# Adafruit_DS2482S-800_Breakout.net
KiCad netlist of a schematic drawn in EAGLE
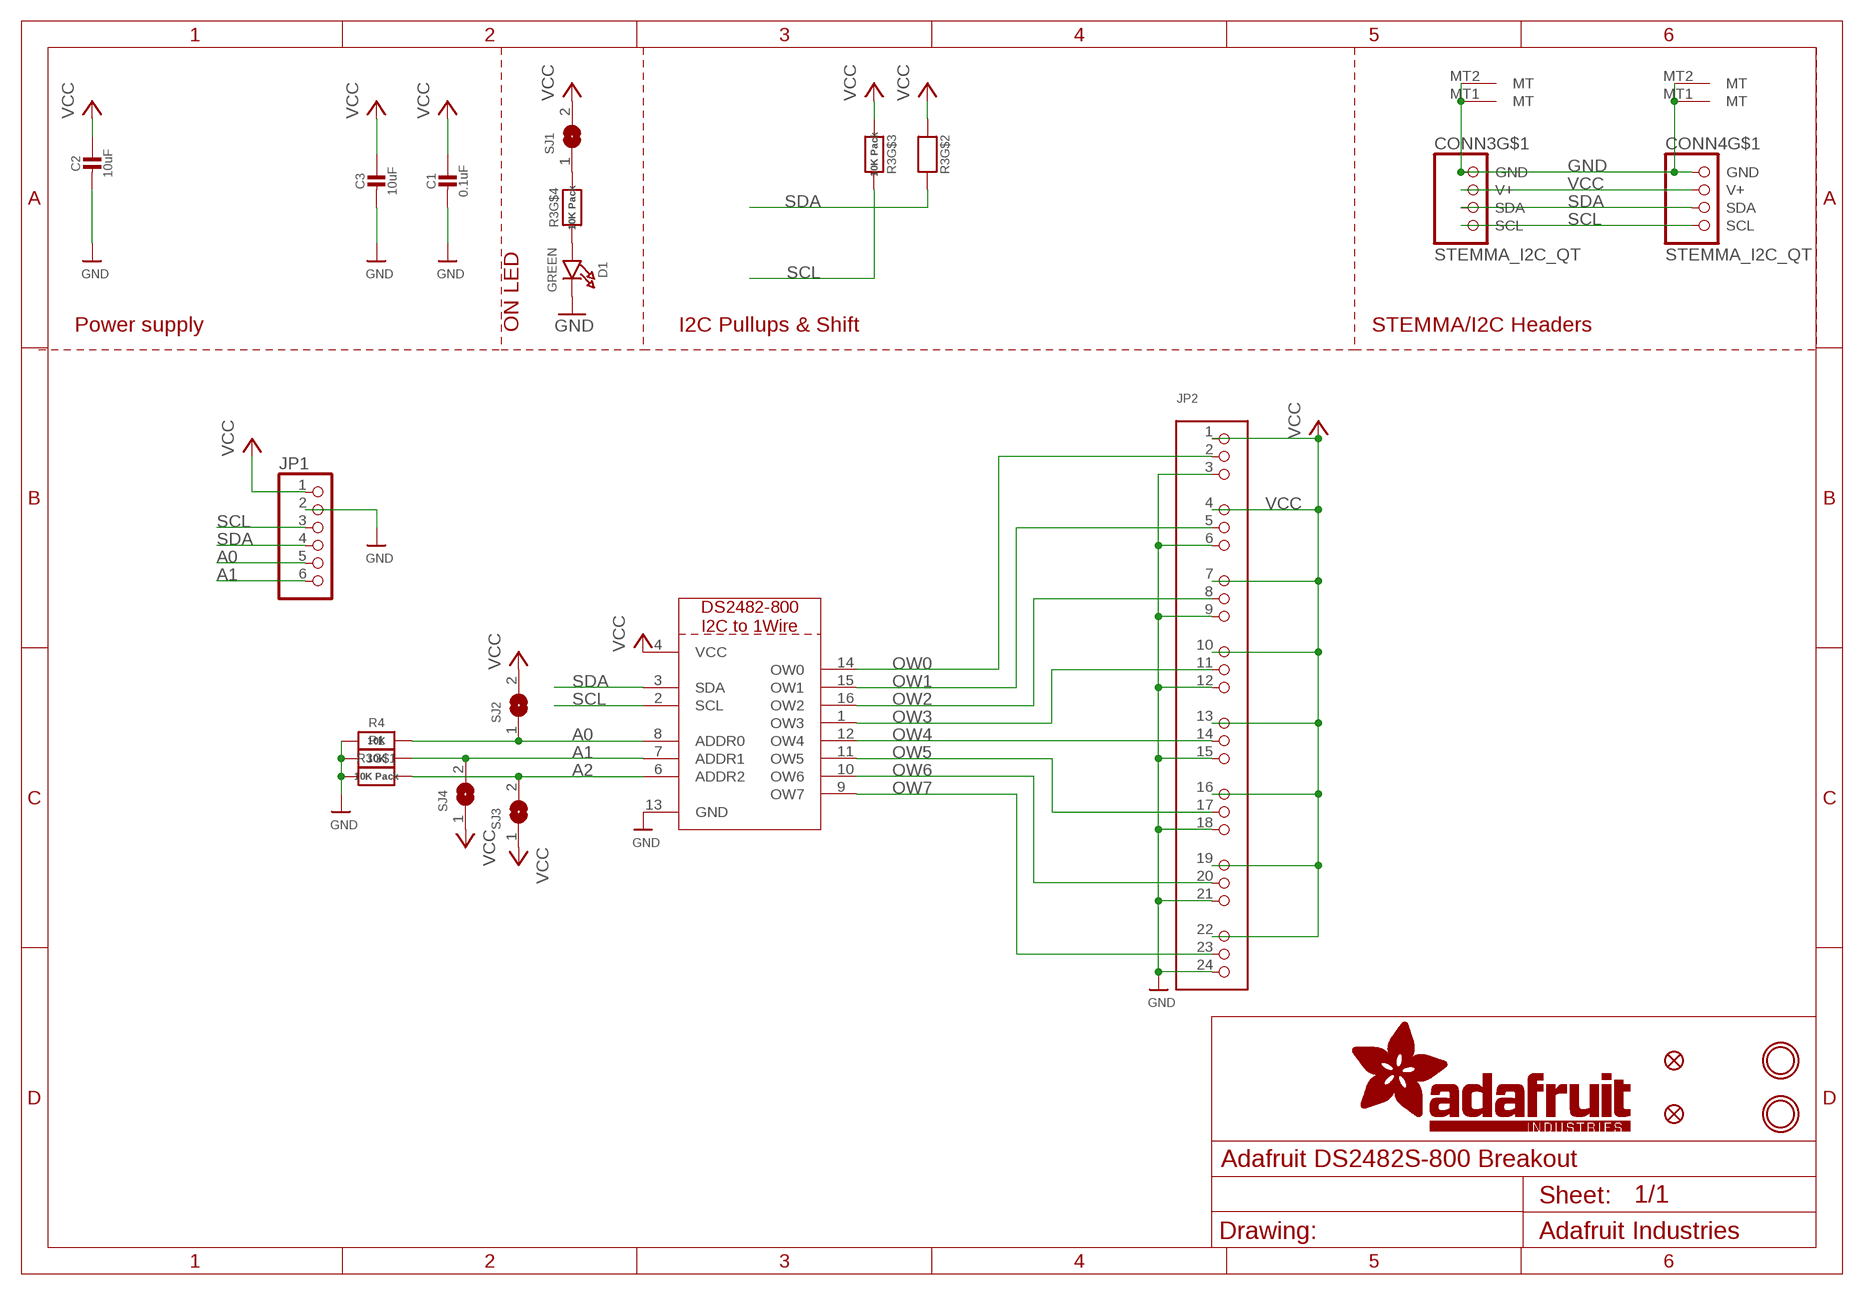
[diagram p0: schematic, sheet 1]

(export (version "E")
  (design (tool "Eeschema 10.0.6"))
  (components
    (comp (ref "C1")
      (value "0.1uF")
      (footprint "eagle-import:0603-NO")
      (libsource (lib "eagle-import") (part "CAP_CERAMIC0603_NO"))
    )
    (comp (ref "C2")
      (value "10uF")
      (footprint "eagle-import:0805-NO")
      (libsource (lib "eagle-import") (part "CAP_CERAMIC0805-NOOUTLINE"))
    )
    (comp (ref "C3")
      (value "10uF")
      (footprint "eagle-import:0805-NO")
      (libsource (lib "eagle-import") (part "CAP_CERAMIC0805-NOOUTLINE"))
    )
    (comp (ref "CONN3")
      (value "STEMMA_I2C_QT")
      (footprint "eagle-import:JST_SH4")
      (libsource (lib "eagle-import") (part "STEMMA_I2C_QT"))
    )
    (comp (ref "CONN4")
      (value "STEMMA_I2C_QT")
      (footprint "eagle-import:JST_SH4")
      (libsource (lib "eagle-import") (part "STEMMA_I2C_QT"))
    )
    (comp (ref "D1")
      (value "GREEN")
      (footprint "eagle-import:CHIPLED_0603_NOOUTLINE")
      (libsource (lib "eagle-import") (part "LED0603_NOOUTLINE"))
    )
    (comp (ref "FID3")
      (value "FIDUCIAL_1MM")
      (footprint "eagle-import:FIDUCIAL_1MM")
      (libsource (lib "eagle-import") (part "FIDUCIAL_1MM"))
    )
    (comp (ref "FID4")
      (value "FIDUCIAL_1MM")
      (footprint "eagle-import:FIDUCIAL_1MM")
      (libsource (lib "eagle-import") (part "FIDUCIAL_1MM"))
    )
    (comp (ref "JP1")
      (value "HEADER-1X670MIL")
      (footprint "eagle-import:1X06_ROUND_70")
      (libsource (lib "eagle-import") (part "HEADER-1X670MIL"))
    )
    (comp (ref "JP2")
      (value "HEADER-3X08")
      (footprint "eagle-import:3X08")
      (libsource (lib "eagle-import") (part "HEADER-3X08"))
    )
    (comp (ref "R1")
      (value "10K")
      (footprint "eagle-import:0603-NO")
      (libsource (lib "eagle-import") (part "RESISTOR_0603_NOOUT"))
    )
    (comp (ref "R3")
      (value "10K Pack")
      (footprint "eagle-import:RESPACK_4X0603")
      (libsource (lib "eagle-import") (part "RESISTOR_4PACK"))
    )
    (comp (ref "R4")
      (value "10K")
      (footprint "eagle-import:0603-NO")
      (libsource (lib "eagle-import") (part "RESISTOR_0603_NOOUT"))
    )
    (comp (ref "SJ1")
      (value "SOLDERJUMPERCLOSED")
      (footprint "eagle-import:SOLDERJUMPER_CLOSEDWIRE")
      (libsource (lib "eagle-import") (part "SOLDERJUMPERCLOSED"))
    )
    (comp (ref "SJ2")
      (value "SOLDERJUMPER")
      (footprint "eagle-import:SOLDERJUMPER_ARROW_NOPASTE")
      (libsource (lib "eagle-import") (part "SOLDERJUMPER"))
    )
    (comp (ref "SJ3")
      (value "SOLDERJUMPER")
      (footprint "eagle-import:SOLDERJUMPER_ARROW_NOPASTE")
      (libsource (lib "eagle-import") (part "SOLDERJUMPER"))
    )
    (comp (ref "SJ4")
      (value "SOLDERJUMPER")
      (footprint "eagle-import:SOLDERJUMPER_ARROW_NOPASTE")
      (libsource (lib "eagle-import") (part "SOLDERJUMPER"))
    )
    (comp (ref "U$19")
      (value "MOUNTINGHOLE2.5")
      (footprint "eagle-import:MOUNTINGHOLE_2.5_PLATED")
      (libsource (lib "eagle-import") (part "MOUNTINGHOLE2.5"))
    )
    (comp (ref "U$21")
      (value "MOUNTINGHOLE2.5")
      (footprint "eagle-import:MOUNTINGHOLE_2.5_PLATED")
      (libsource (lib "eagle-import") (part "MOUNTINGHOLE2.5"))
    )
    (comp (ref "X1")
      (value "DS2482-800")
      (footprint "eagle-import:SO16")
      (libsource (lib "eagle-import") (part "DS2482-800"))
    )
  )
  (nets
    (net (code "1") (name "/A0") (class "Default")
      (node (ref "JP1") (pin "5") (pinfunction "5_5") (pintype "passive"))
      (node (ref "R4") (pin "2") (pinfunction "2_2") (pintype "passive"))
      (node (ref "SJ2") (pin "1") (pinfunction "1_1") (pintype "passive"))
      (node (ref "X1") (pin "8") (pinfunction "ADDR0_8") (pintype "bidirectional"))
    )
    (net (code "2") (name "/A1") (class "Default")
      (node (ref "JP1") (pin "6") (pinfunction "6_6") (pintype "passive"))
      (node (ref "R1") (pin "2") (pinfunction "2_2") (pintype "passive"))
      (node (ref "SJ4") (pin "2") (pinfunction "2_2") (pintype "passive"))
      (node (ref "X1") (pin "7") (pinfunction "ADDR1_7") (pintype "bidirectional"))
    )
    (net (code "3") (name "/A2") (class "Default")
      (node (ref "R3") (pin "8") (pinfunction "2_8") (pintype "passive"))
      (node (ref "SJ3") (pin "2") (pinfunction "2_2") (pintype "passive"))
      (node (ref "X1") (pin "6") (pinfunction "ADDR2_6") (pintype "bidirectional"))
    )
    (net (code "4") (name "/OW0") (class "Default")
      (node (ref "JP2") (pin "2") (pinfunction "2_2") (pintype "passive"))
      (node (ref "X1") (pin "14") (pinfunction "OW0_14") (pintype "bidirectional"))
    )
    (net (code "5") (name "/OW1") (class "Default")
      (node (ref "JP2") (pin "5") (pinfunction "5_5") (pintype "passive"))
      (node (ref "X1") (pin "15") (pinfunction "OW1_15") (pintype "bidirectional"))
    )
    (net (code "6") (name "/OW2") (class "Default")
      (node (ref "JP2") (pin "8") (pinfunction "8_8") (pintype "passive"))
      (node (ref "X1") (pin "16") (pinfunction "OW2_16") (pintype "bidirectional"))
    )
    (net (code "7") (name "/OW3") (class "Default")
      (node (ref "JP2") (pin "11") (pinfunction "11_11") (pintype "passive"))
      (node (ref "X1") (pin "1") (pinfunction "OW3_1") (pintype "bidirectional"))
    )
    (net (code "8") (name "/OW4") (class "Default")
      (node (ref "JP2") (pin "14") (pinfunction "14_14") (pintype "passive"))
      (node (ref "X1") (pin "12") (pinfunction "OW4_12") (pintype "bidirectional"))
    )
    (net (code "9") (name "/OW5") (class "Default")
      (node (ref "JP2") (pin "17") (pinfunction "17_17") (pintype "passive"))
      (node (ref "X1") (pin "11") (pinfunction "OW5_11") (pintype "bidirectional"))
    )
    (net (code "10") (name "/OW6") (class "Default")
      (node (ref "JP2") (pin "20") (pinfunction "20_20") (pintype "passive"))
      (node (ref "X1") (pin "10") (pinfunction "OW6_10") (pintype "bidirectional"))
    )
    (net (code "11") (name "/OW7") (class "Default")
      (node (ref "JP2") (pin "23") (pinfunction "23_23") (pintype "passive"))
      (node (ref "X1") (pin "9") (pinfunction "OW7_9") (pintype "bidirectional"))
    )
    (net (code "12") (name "/SCL") (class "Default")
      (node (ref "CONN3") (pin "4") (pinfunction "SCL_4") (pintype "passive"))
      (node (ref "CONN4") (pin "4") (pinfunction "SCL_4") (pintype "passive"))
      (node (ref "JP1") (pin "3") (pinfunction "3_3") (pintype "passive"))
      (node (ref "R3") (pin "6") (pinfunction "2_6") (pintype "passive"))
      (node (ref "X1") (pin "2") (pinfunction "SCL_2") (pintype "bidirectional"))
    )
    (net (code "13") (name "/SDA") (class "Default")
      (node (ref "CONN3") (pin "3") (pinfunction "SDA_3") (pintype "passive"))
      (node (ref "CONN4") (pin "3") (pinfunction "SDA_3") (pintype "passive"))
      (node (ref "JP1") (pin "4") (pinfunction "4_4") (pintype "passive"))
      (node (ref "R3") (pin "7") (pinfunction "2_7") (pintype "passive"))
      (node (ref "X1") (pin "3") (pinfunction "SDA_3") (pintype "bidirectional"))
    )
    (net (code "14") (name "GND") (class "Default")
      (node (ref "C1") (pin "2") (pinfunction "2_2") (pintype "passive"))
      (node (ref "C2") (pin "2") (pinfunction "2_2") (pintype "passive"))
      (node (ref "C3") (pin "2") (pinfunction "2_2") (pintype "passive"))
      (node (ref "CONN3") (pin "1") (pinfunction "GND_1") (pintype "passive"))
      (node (ref "CONN3") (pin "MT1") (pinfunction "MT_MT1") (pintype "bidirectional"))
      (node (ref "CONN3") (pin "MT2") (pinfunction "MT_MT2") (pintype "bidirectional"))
      (node (ref "CONN4") (pin "1") (pinfunction "GND_1") (pintype "passive"))
      (node (ref "CONN4") (pin "MT1") (pinfunction "MT_MT1") (pintype "bidirectional"))
      (node (ref "CONN4") (pin "MT2") (pinfunction "MT_MT2") (pintype "bidirectional"))
      (node (ref "D1") (pin "C") (pinfunction "C_C") (pintype "passive"))
      (node (ref "JP1") (pin "2") (pinfunction "2_2") (pintype "passive"))
      (node (ref "JP2") (pin "12") (pinfunction "12_12") (pintype "passive"))
      (node (ref "JP2") (pin "15") (pinfunction "15_15") (pintype "passive"))
      (node (ref "JP2") (pin "18") (pinfunction "18_18") (pintype "passive"))
      (node (ref "JP2") (pin "21") (pinfunction "21_21") (pintype "passive"))
      (node (ref "JP2") (pin "24") (pinfunction "24_24") (pintype "passive"))
      (node (ref "JP2") (pin "3") (pinfunction "3_3") (pintype "passive"))
      (node (ref "JP2") (pin "6") (pinfunction "6_6") (pintype "passive"))
      (node (ref "JP2") (pin "9") (pinfunction "9_9") (pintype "passive"))
      (node (ref "R1") (pin "1") (pinfunction "1_1") (pintype "passive"))
      (node (ref "R3") (pin "1") (pinfunction "1_1") (pintype "passive"))
      (node (ref "R4") (pin "1") (pinfunction "1_1") (pintype "passive"))
      (node (ref "X1") (pin "13") (pinfunction "GND_13") (pintype "power_in"))
    )
    (net (code "15") (name "Net-(R3D-1)") (class "Default")
      (node (ref "D1") (pin "A") (pinfunction "A_A") (pintype "passive"))
      (node (ref "R3") (pin "4") (pinfunction "1_4") (pintype "passive"))
    )
    (net (code "16") (name "Net-(R3D-2)") (class "Default")
      (node (ref "R3") (pin "5") (pinfunction "2_5") (pintype "passive"))
      (node (ref "SJ1") (pin "1") (pinfunction "1_1") (pintype "passive"))
    )
    (net (code "17") (name "VCC") (class "Default")
      (node (ref "C1") (pin "1") (pinfunction "1_1") (pintype "passive"))
      (node (ref "C2") (pin "1") (pinfunction "1_1") (pintype "passive"))
      (node (ref "C3") (pin "1") (pinfunction "1_1") (pintype "passive"))
      (node (ref "CONN3") (pin "2") (pinfunction "V+_2") (pintype "passive"))
      (node (ref "CONN4") (pin "2") (pinfunction "V+_2") (pintype "passive"))
      (node (ref "JP1") (pin "1") (pinfunction "1_1") (pintype "passive"))
      (node (ref "JP2") (pin "1") (pinfunction "1_1") (pintype "passive"))
      (node (ref "JP2") (pin "10") (pinfunction "10_10") (pintype "passive"))
      (node (ref "JP2") (pin "13") (pinfunction "13_13") (pintype "passive"))
      (node (ref "JP2") (pin "16") (pinfunction "16_16") (pintype "passive"))
      (node (ref "JP2") (pin "19") (pinfunction "19_19") (pintype "passive"))
      (node (ref "JP2") (pin "22") (pinfunction "22_22") (pintype "passive"))
      (node (ref "JP2") (pin "4") (pinfunction "4_4") (pintype "passive"))
      (node (ref "JP2") (pin "7") (pinfunction "7_7") (pintype "passive"))
      (node (ref "R3") (pin "2") (pinfunction "1_2") (pintype "passive"))
      (node (ref "R3") (pin "3") (pinfunction "1_3") (pintype "passive"))
      (node (ref "SJ1") (pin "2") (pinfunction "2_2") (pintype "passive"))
      (node (ref "SJ2") (pin "2") (pinfunction "2_2") (pintype "passive"))
      (node (ref "SJ3") (pin "1") (pinfunction "1_1") (pintype "passive"))
      (node (ref "SJ4") (pin "1") (pinfunction "1_1") (pintype "passive"))
      (node (ref "X1") (pin "4") (pinfunction "VCC_4") (pintype "power_in"))
    )
  )
)
